# Serial_Power_Supply_-_Main.net
KiCad netlist of a schematic drawn in Altium Designer
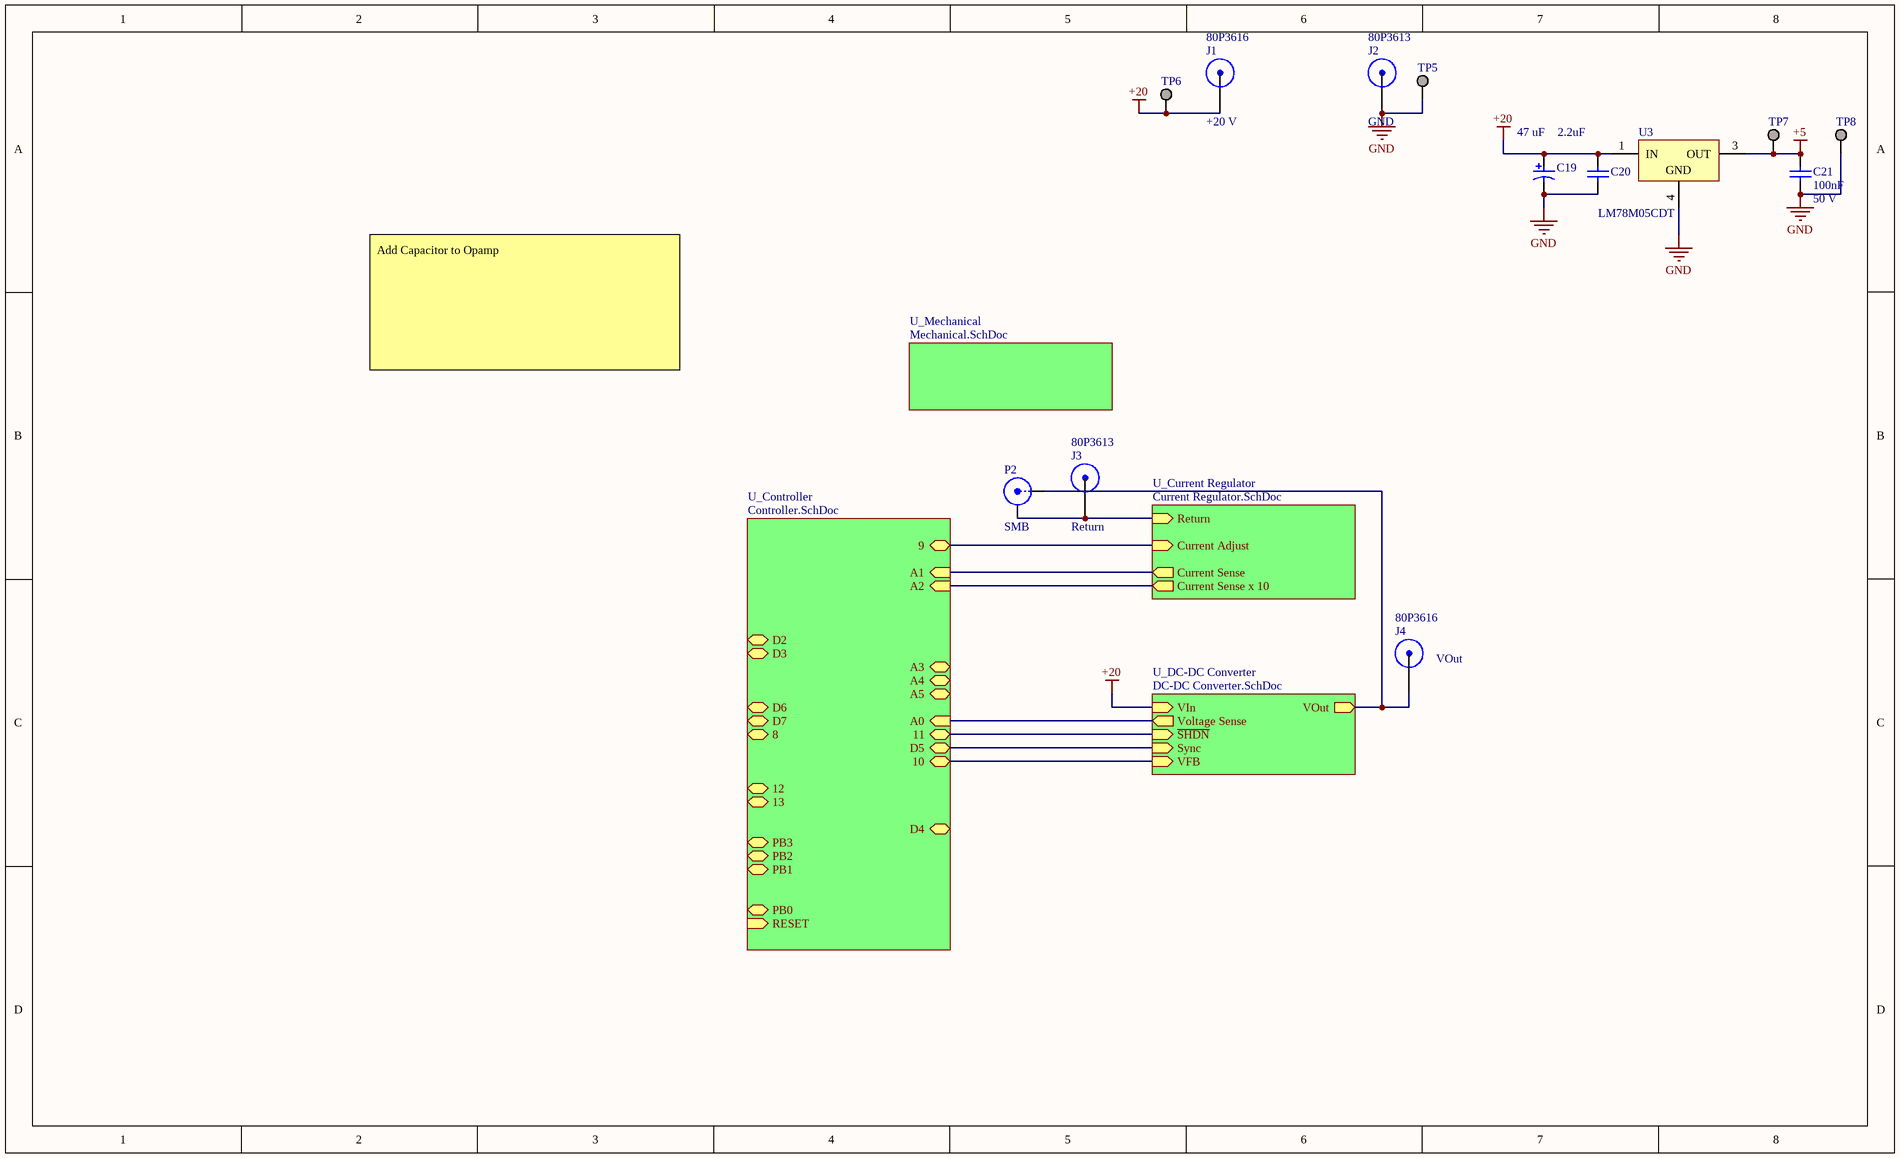
[diagram p0: Serial Power Supply - Main.SchDoc]

(export (version "E")
  (design (tool "Eeschema 10.0.6"))
  (components
    (comp (ref "C19")
      (value "UCZ1J470MCS1GS")
      (footprint "NIC-CAPA2-10X10_V")
      (fields (field (name "RATED CAPACITANCE") "47 uF") (field (name "MANUFACTURER") "Nichicon"))
      (libsource (lib "Altium Content Vault") (part "NIC-CAP-P-2"))
    )
    (comp (ref "C20")
      (value "2.2uF")
      (footprint "CAPC1812(4532)280_L")
      (description "CAP 2.2uF 100V ±10% 1812 (4532 Metric) Thickness 2.8mm SMD")
      (fields (field (name "TOLERANCE") "Â±10%") (field (name "Comment") "CAP 2.2uF 100V 1812(4532)"))
      (libsource (lib "Altium Content Vault") (part "CAP"))
    )
    (comp (ref "C21")
      (value "100nF")
      (footprint "CAPC1206(3216)100_L")
      (description "CAP 100nF 50V ±10% 1206 (3216 Metric) Thickness 1mm SMD")
      (fields
        (field (name "TOLERANCE") "Â±10%")
        (field (name "RATED VOLTAGE") "50 V")
        (field (name "Comment") "CAP 100nF 50V 1206(3216)")
      )
      (libsource (lib "Altium Content Vault") (part "CAP"))
    )
    (comp (ref "J1")
      (value "+20 V")
      (footprint "PCB-1keg917tfggg2k36z9zw-1")
      (description "Banana Socket, 20a, 4mm, Pcb, Red")
      (fields (field (name "SUPPLIER PART NUMBER 1") "80P3616"))
      (libsource (lib "SYM-20399854-2") (part "SYM-20399854-1"))
    )
    (comp (ref "J2")
      (value "GND")
      (footprint "PCB-1keg917tfggg2k36z9zw-1")
      (description "Banana Socket, 20a, 4mm, Pcb, Black")
      (fields (field (name "SUPPLIER PART NUMBER 1") "80P3613"))
      (libsource (lib "SYM-20399854-2") (part "SYM-20399854-1"))
    )
    (comp (ref "J3")
      (value "Return")
      (footprint "PCB-1keg917tfggg2k36z9zw-1")
      (description "Banana Socket, 20a, 4mm, Pcb, Black")
      (fields (field (name "SUPPLIER PART NUMBER 1") "80P3613"))
      (libsource (lib "SYM-20399854-2") (part "SYM-20399854-1"))
    )
    (comp (ref "J4")
      (value "VOut")
      (footprint "PCB-1keg917tfggg2k36z9zw-1")
      (description "Banana Socket, 20a, 4mm, Pcb, Red")
      (fields (field (name "SUPPLIER PART NUMBER 1") "80P3616"))
      (libsource (lib "SYM-20399854-2") (part "SYM-20399854-1"))
    )
    (comp (ref "P2")
      (value "SMB")
      (footprint "SMB_V-RJ45")
      (description "SMB Straight Connector")
      (fields (field (name "PUBLISHER") "Altium Limited"))
      (libsource (lib "Miscellaneous Connectors") (part "SMB"))
    )
    (comp (ref "TP5")
      (value "GND")
      (footprint "KSTN-1502-2")
      (description "Terminal DBL Turret, Through Hole, RoHS")
      (libsource (lib "Altium Content Vault") (part "KSTN-1502-2"))
    )
    (comp (ref "TP6")
      (value "+20V")
      (footprint "KSTN-1502-2")
      (description "Terminal DBL Turret, Through Hole, RoHS")
      (libsource (lib "Altium Content Vault") (part "KSTN-1502-2"))
    )
    (comp (ref "TP7")
      (value "+5 V")
      (footprint "KSTN-1502-2")
      (description "Terminal DBL Turret, Through Hole, RoHS")
      (libsource (lib "Altium Content Vault") (part "KSTN-1502-2"))
    )
    (comp (ref "TP8")
      (value "GND")
      (footprint "KSTN-1502-2")
      (description "Terminal DBL Turret, Through Hole, RoHS")
      (libsource (lib "Altium Content Vault") (part "KSTN-1502-2"))
    )
    (comp (ref "U3")
      (value "LM78M05CDT")
      (footprint "TD03B_L")
      (description "3-Terminal Positive Voltage Regulators, 3-pin TO-252")
      (fields (field (name "MANUFACTURER") "National Semiconductor"))
      (libsource (lib "Altium Content Vault") (part "PM-REG-LM78M05-SOT3"))
    )
  )
  (nets
    (net (code "1") (name "+5") (class "Default")
      (node (ref "C21") (pin "1") (pinfunction "1_1") (pintype "passive"))
      (node (ref "TP7") (pin "1") (pintype "passive"))
      (node (ref "U3") (pin "3") (pinfunction "OUT_3") (pintype "power_in"))
    )
    (net (code "2") (name "+20") (class "Default")
      (node (ref "C19") (pin "1") (pinfunction "1_1") (pintype "passive"))
      (node (ref "C20") (pin "2") (pinfunction "2_2") (pintype "passive"))
      (node (ref "J1") (pin "1") (pinfunction "1_1") (pintype "passive"))
      (node (ref "TP6") (pin "1") (pintype "passive"))
      (node (ref "U3") (pin "1") (pinfunction "IN_1") (pintype "power_in"))
    )
    (net (code "25") (name "/Return") (class "Default")
      (node (ref "J3") (pin "1") (pinfunction "1_1") (pintype "passive"))
      (node (ref "P2") (pin "2") (pinfunction "Y_2") (pintype "passive"))
    )
    (net (code "26") (name "/VOut") (class "Default")
      (node (ref "J4") (pin "1") (pinfunction "1_1") (pintype "passive"))
      (node (ref "P2") (pin "1") (pinfunction "X_1") (pintype "passive"))
    )
    (net (code "28") (name "GND") (class "Default")
      (node (ref "C19") (pin "2") (pinfunction "2_2") (pintype "passive"))
      (node (ref "C20") (pin "1") (pinfunction "1_1") (pintype "passive"))
      (node (ref "C21") (pin "2") (pinfunction "2_2") (pintype "passive"))
      (node (ref "J2") (pin "1") (pinfunction "1_1") (pintype "passive"))
      (node (ref "TP5") (pin "1") (pintype "passive"))
      (node (ref "TP8") (pin "1") (pintype "passive"))
      (node (ref "U3") (pin "4") (pinfunction "GND_4") (pintype "power_in"))
    )
  )
)
